# Connectors.net
KiCad netlist of a schematic drawn in Altium Designer
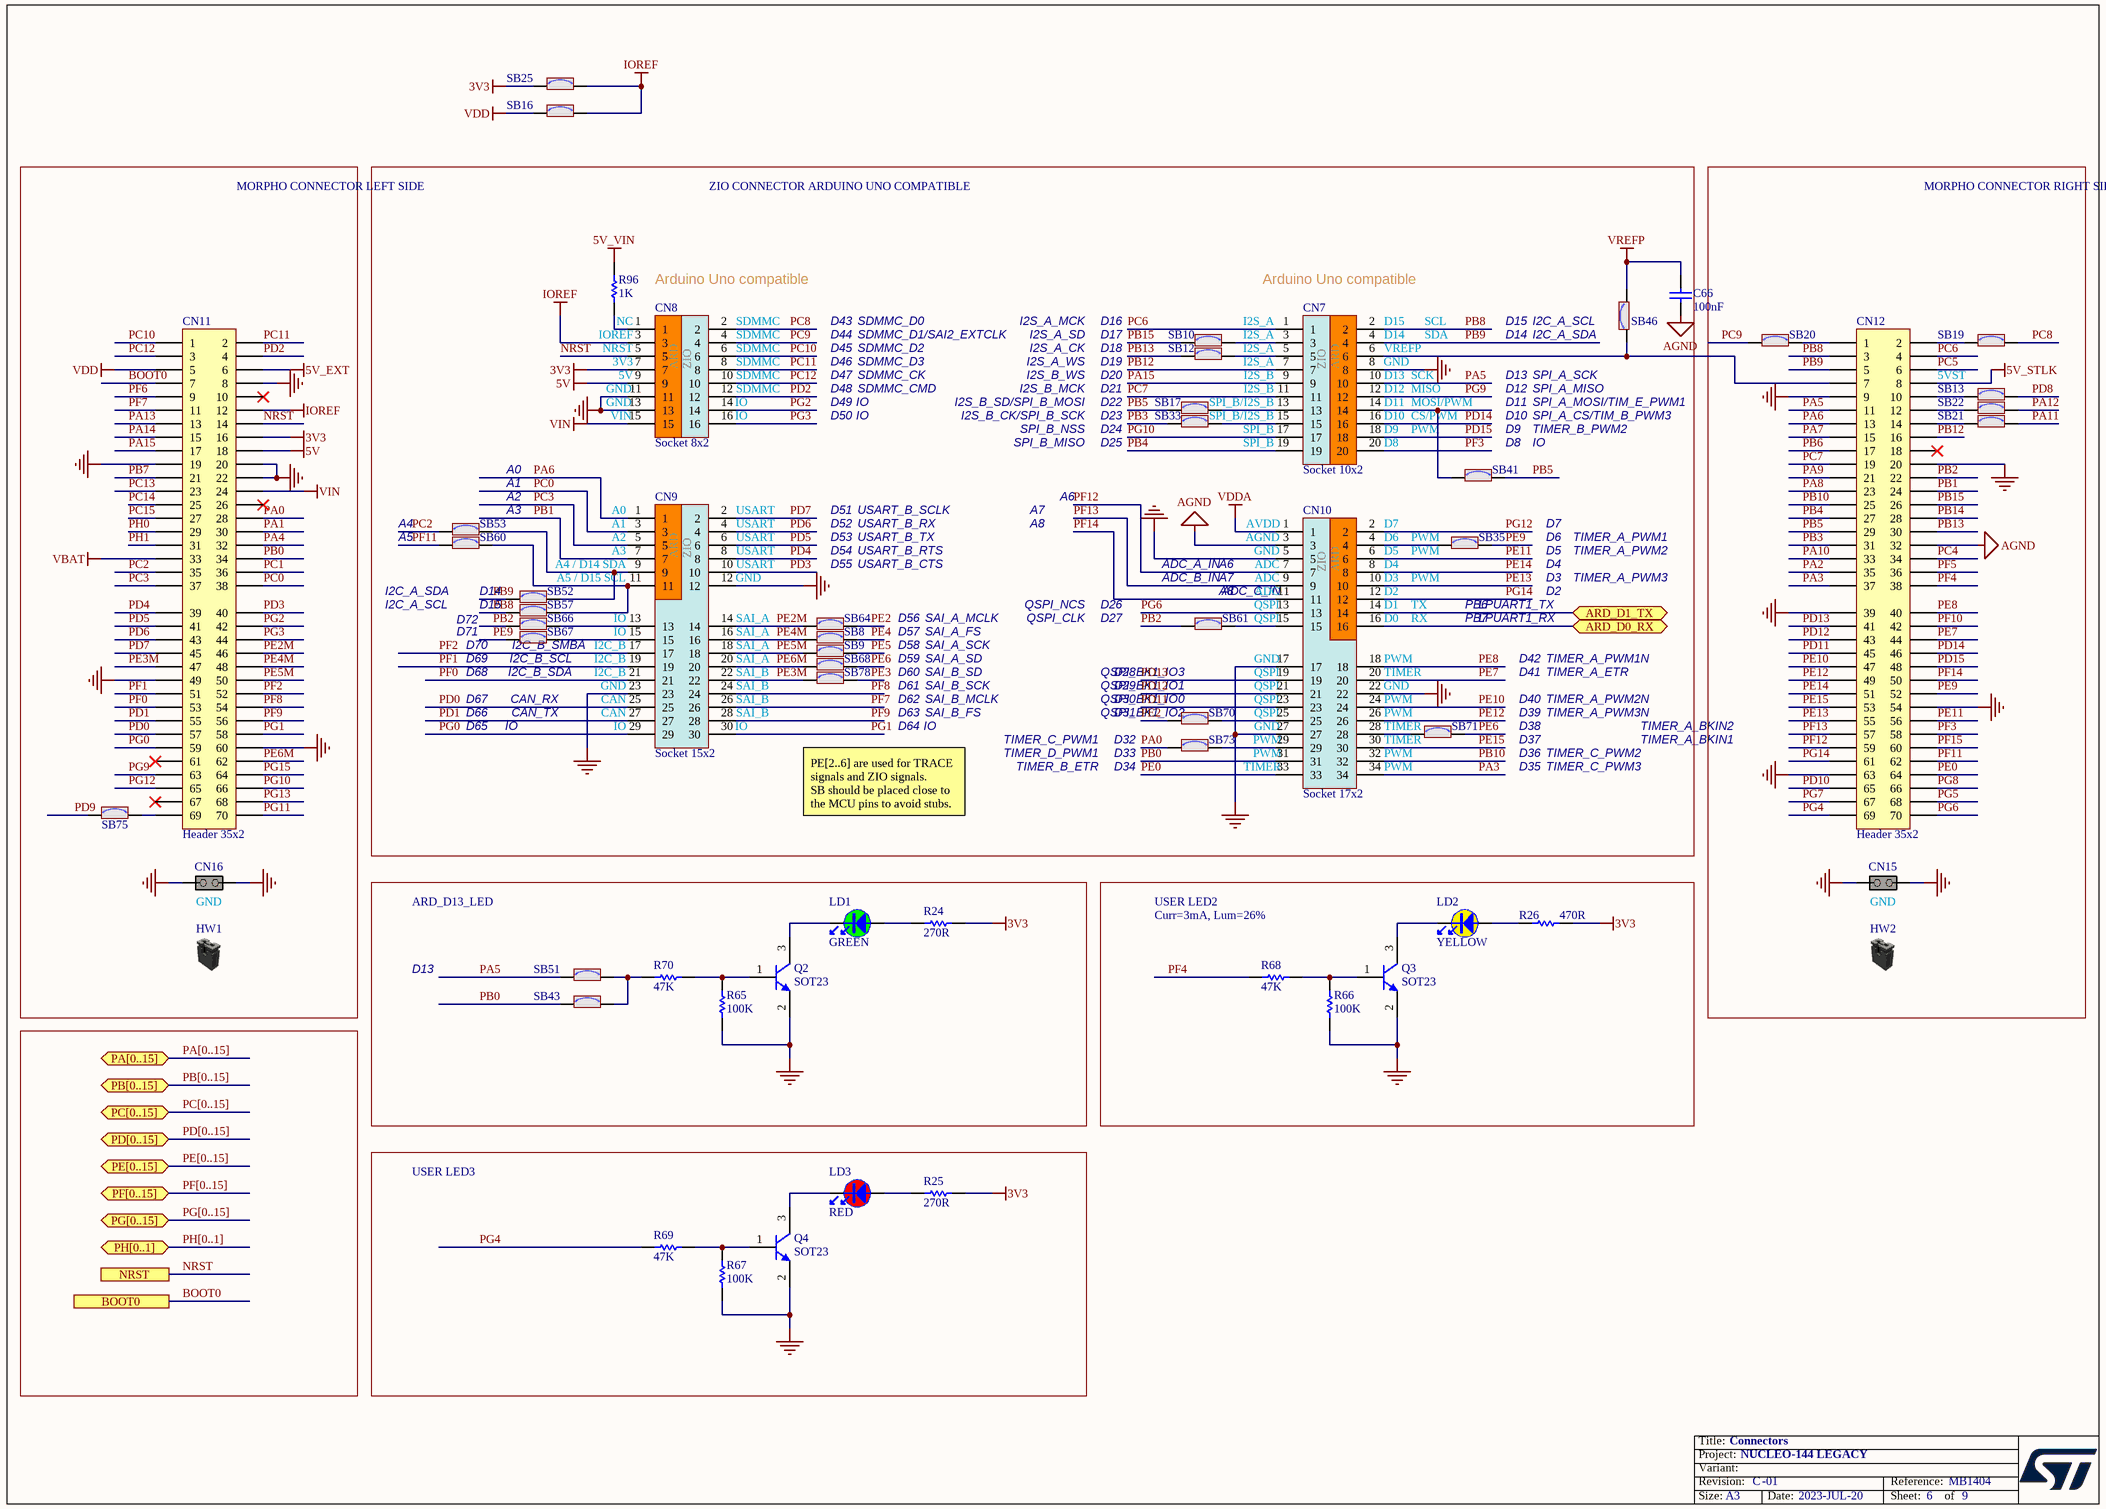
[diagram p0: Connectors.SchDoc]

(export (version "E")
  (design (tool "Eeschema 10.0.6"))
  (components
    (comp (ref "C66")
      (value "100nF")
      (footprint "C0603")
      (description "Capacitor, MLCC, 100nF, 6V3, X5R, +/-10%, 0603, T=0.8mm")
      (fields (field (name "INTERNAL_PART_NUMBER") "MCD-02119") (field (name "MANUFACTURER") "KEMET"))
      (libsource (lib "MCD_PARTS_database") (part "Capacitor"))
    )
    (comp (ref "CN7")
      (value "Socket 10x2")
      (footprint "MCD_PARTS:CON_SAMTEC_SSQ-110-23-F-D")
      (description "Socket, 10x2, 2.54mm, VR, TH, T=8.51mm/10mm")
      (fields (field (name "INTERNAL_PART_NUMBER") "MCD-02953") (field (name "MANUFACTURER") "SAMTEC"))
      (libsource (lib "MCD_PARTS_database") (part "Socket 10x2_N144_ARD"))
    )
    (comp (ref "CN8")
      (value "Socket 8x2")
      (footprint "MCD_PARTS:CON_SAMTEC_SSQ-108-23-F-D")
      (description "Socket, 8x2, 2.54mm, VR, TH, T=8.51mm/10mm")
      (fields (field (name "INTERNAL_PART_NUMBER") "MCD-02951") (field (name "MANUFACTURER") "SAMTEC"))
      (libsource (lib "MCD_PARTS_database") (part "Socket 8x2_N144_ARD"))
    )
    (comp (ref "CN9")
      (value "Socket 15x2")
      (footprint "MCD_PARTS:CON_SAMTEC_SSQ-115-23-F-D")
      (description "Socket, 15x2, 2.54mm, VR, TH, T=8.51mm/10mm")
      (fields (field (name "INTERNAL_PART_NUMBER") "MCD-02952") (field (name "MANUFACTURER") "SAMTEC"))
      (libsource (lib "MCD_PARTS_database") (part "Socket 15x2_N144_ARD"))
    )
    (comp (ref "CN10")
      (value "Socket 17x2")
      (footprint "MCD_PARTS:CON_SAMTEC_SSQ-117-23-F-D")
      (description "Socket, 17x2, 2.54mm, VR, TH, T=8.51mm/10mm")
      (fields (field (name "INTERNAL_PART_NUMBER") "MCD-02954") (field (name "MANUFACTURER") "SAMTEC"))
      (libsource (lib "MCD_PARTS_database") (part "Socket 17x2_N144_ARD"))
    )
    (comp (ref "CN11")
      (value "Header 35x2")
      (footprint "MCD_PARTS:CON_SAMTEC_TSW-135-07-X-D")
      (description "Header, 35x2, 2,54mm, VR, TH, Height 5.84mm/2.54mm")
      (fields
        (field (name "INTERNAL_PART_NUMBER") "MCD-01210")
        (field (name "MANUFACTURER_PART_NUMBER") "TSW-135-07-x-D")
        (field (name "PROVIDED_BY") "SUBCO")
      )
      (libsource (lib "MCD_PARTS_database") (part "Header 35x2"))
    )
    (comp (ref "CN12")
      (value "Header 35x2")
      (footprint "MCD_PARTS:CON_SAMTEC_TSW-135-07-X-D")
      (description "Header, 35x2, 2,54mm, VR, TH, Height 5.84mm/2.54mm")
      (fields
        (field (name "INTERNAL_PART_NUMBER") "MCD-01210")
        (field (name "MANUFACTURER_PART_NUMBER") "TSW-135-07-x-D")
        (field (name "PROVIDED_BY") "SUBCO")
      )
      (libsource (lib "MCD_PARTS_database") (part "Header 35x2"))
    )
    (comp (ref "CN15")
      (value "Jumper_Header 2x1")
      (footprint "MCD_PARTS:CON_SAMTEC_TSW-102-09-X-S")
      (description "Header, 2x1, 2,54mm, VR, TH, Height 5.84mm/10.16mm")
      (fields
        (field (name "INTERNAL_PART_NUMBER") "MCD-00214")
        (field (name "MANUFACTURER_PART_NUMBER") "TSW-102-09-x-S")
        (field (name "PROVIDED_BY") "SUBCO")
      )
      (libsource (lib "MCD_PARTS_database") (part "Jumper_Header 2x1"))
    )
    (comp (ref "CN16")
      (value "Jumper_Header 2x1")
      (footprint "MCD_PARTS:CON_SAMTEC_TSW-102-09-X-S")
      (description "Header, 2x1, 2,54mm, VR, TH, Height 5.84mm/10.16mm")
      (fields
        (field (name "INTERNAL_PART_NUMBER") "MCD-00214")
        (field (name "MANUFACTURER_PART_NUMBER") "TSW-102-09-x-S")
        (field (name "PROVIDED_BY") "SUBCO")
      )
      (libsource (lib "MCD_PARTS_database") (part "Jumper_Header 2x1"))
    )
    (comp (ref "HW1")
      (value "Shunt Black 2.54mm")
      (description "SHUNT 2.54mm BLACK")
      (fields
        (field (name "INTERNAL_PART_NUMBER") "MCD-00043")
        (field (name "MANUFACTURER_PART_NUMBER") "SNT-100-BK-G")
        (field (name "PROVIDED_BY") "SUBCO")
      )
      (libsource (lib "MCD_PARTS_database") (part "Shunt Black 2.54mm"))
    )
    (comp (ref "HW2")
      (value "Shunt Black 2.54mm")
      (description "SHUNT 2.54mm BLACK")
      (fields
        (field (name "INTERNAL_PART_NUMBER") "MCD-00043")
        (field (name "MANUFACTURER_PART_NUMBER") "SNT-100-BK-G")
        (field (name "PROVIDED_BY") "SUBCO")
      )
      (libsource (lib "MCD_PARTS_database") (part "Shunt Black 2.54mm"))
    )
    (comp (ref "LD1")
      (value "GREEN")
      (footprint "MCD_PARTS:LED_0603_OSRAM_LG-Q396-PS-35_GREEN_1A2K_H0P4")
      (description "LED Green, 0603 SMD, Forward Voltage Typ=2V, Max=2.5V")
      (fields
        (field (name "INTERNAL_PART_NUMBER") "MCD-00588")
        (field (name "MANUFACTURER_PART_NUMBER") "LG Q396-PS-35")
        (field (name "PROVIDED_BY") "SUBCO")
      )
      (libsource (lib "MCD_PARTS_database") (part "LED_green"))
    )
    (comp (ref "LD2")
      (value "YELLOW")
      (footprint "MCD_PARTS:LED_0603_OSRAM_LY-Q396-P1Q2-36_YELLOW_1A2K_H0P4")
      (description "LED Yellow, 0603 SMD, Forward Voltage min=1.7V, Typ=2V, Max=2.3V")
      (fields
        (field (name "INTERNAL_PART_NUMBER") "MCD-01061")
        (field (name "MANUFACTURER_PART_NUMBER") "LY Q396-P1Q2-36")
        (field (name "PROVIDED_BY") "SUBCO")
      )
      (libsource (lib "MCD_PARTS_database") (part "LED_yellow"))
    )
    (comp (ref "LD3")
      (value "RED")
      (footprint "MCD_PARTS:LED_0603_OSRAM_LS-Q976-NR-1_RED_1A2K_H0P8")
      (description "LED Red, 0603 SMD, Forward Voltage Typ=2V, Max=2.5V")
      (fields
        (field (name "INTERNAL_PART_NUMBER") "MCD-00586")
        (field (name "MANUFACTURER_PART_NUMBER") "LS Q976-NR-1")
        (field (name "PROVIDED_BY") "SUBCO")
      )
      (libsource (lib "MCD_PARTS_database") (part "LED_red"))
    )
    (comp (ref "Q2")
      (value "SOT23")
      (footprint "MCD_PARTS:NPN_SOT23")
      (description "NPN Bipolar Transistor")
      (fields
        (field (name "INTERNAL_PART_NUMBER") "MCD-00073")
        (field (name "MANUFACTURER_PART_NUMBER") "BSR14")
        (field (name "PROVIDED_BY") "SUBCO")
      )
      (libsource (lib "MCD_PARTS_database") (part "9013-SOT23"))
    )
    (comp (ref "Q3")
      (value "SOT23")
      (footprint "MCD_PARTS:NPN_SOT23")
      (description "NPN Bipolar Transistor")
      (fields
        (field (name "INTERNAL_PART_NUMBER") "MCD-00073")
        (field (name "MANUFACTURER_PART_NUMBER") "BSR14")
        (field (name "PROVIDED_BY") "SUBCO")
      )
      (libsource (lib "MCD_PARTS_database") (part "9013-SOT23"))
    )
    (comp (ref "Q4")
      (value "SOT23")
      (footprint "MCD_PARTS:NPN_SOT23")
      (description "NPN Bipolar Transistor")
      (fields
        (field (name "INTERNAL_PART_NUMBER") "MCD-00073")
        (field (name "MANUFACTURER_PART_NUMBER") "BSR14")
        (field (name "PROVIDED_BY") "SUBCO")
      )
      (libsource (lib "MCD_PARTS_database") (part "9013-SOT23"))
    )
    (comp (ref "R24")
      (value "270R")
      (footprint "MCD_PARTS:R0402")
      (description "Resistor,270R,0402,1%,1/16W")
      (fields
        (field (name "INTERNAL_PART_NUMBER") "MCD-00441")
        (field (name "MANUFACTURER_PART_NUMBER") "RC0402FR-07270RL")
        (field (name "PROVIDED_BY") "SUBCO")
      )
      (libsource (lib "MCD_PARTS_database") (part "Resistor"))
    )
    (comp (ref "R25")
      (value "270R")
      (footprint "MCD_PARTS:R0402")
      (description "Resistor,270R,0402,1%,1/16W")
      (fields
        (field (name "INTERNAL_PART_NUMBER") "MCD-00441")
        (field (name "MANUFACTURER_PART_NUMBER") "RC0402FR-07270RL")
        (field (name "PROVIDED_BY") "SUBCO")
      )
      (libsource (lib "MCD_PARTS_database") (part "Resistor"))
    )
    (comp (ref "R26")
      (value "470R")
      (footprint "MCD_PARTS:R0402")
      (description "Resistor,470R,0402,1%,1/16W")
      (fields
        (field (name "INTERNAL_PART_NUMBER") "MCD-00178")
        (field (name "MANUFACTURER_PART_NUMBER") "RC0402FR-07470RL")
        (field (name "PROVIDED_BY") "SUBCO")
      )
      (libsource (lib "MCD_PARTS_database") (part "Resistor"))
    )
    (comp (ref "R65")
      (value "100K")
      (footprint "MCD_PARTS:R0603")
      (description "Resistor,100K,0603,1%,1/10W")
      (fields
        (field (name "INTERNAL_PART_NUMBER") "MCD-00223")
        (field (name "MANUFACTURER_PART_NUMBER") "RC0603FR-07100KL")
        (field (name "PROVIDED_BY") "SUBCO")
      )
      (libsource (lib "MCD_PARTS_database") (part "Resistor"))
    )
    (comp (ref "R66")
      (value "100K")
      (footprint "MCD_PARTS:R0603")
      (description "Resistor,100K,0603,1%,1/10W")
      (fields
        (field (name "INTERNAL_PART_NUMBER") "MCD-00223")
        (field (name "MANUFACTURER_PART_NUMBER") "RC0603FR-07100KL")
        (field (name "PROVIDED_BY") "SUBCO")
      )
      (libsource (lib "MCD_PARTS_database") (part "Resistor"))
    )
    (comp (ref "R67")
      (value "100K")
      (footprint "MCD_PARTS:R0603")
      (description "Resistor,100K,0603,1%,1/10W")
      (fields
        (field (name "INTERNAL_PART_NUMBER") "MCD-00223")
        (field (name "MANUFACTURER_PART_NUMBER") "RC0603FR-07100KL")
        (field (name "PROVIDED_BY") "SUBCO")
      )
      (libsource (lib "MCD_PARTS_database") (part "Resistor"))
    )
    (comp (ref "R68")
      (value "47K")
      (footprint "MCD_PARTS:R0603")
      (description "Resistor,47K,0603,1%,1/10W")
      (fields
        (field (name "INTERNAL_PART_NUMBER") "MCD-00222")
        (field (name "MANUFACTURER_PART_NUMBER") "RC0603FR-0747KL")
        (field (name "PROVIDED_BY") "SUBCO")
      )
      (libsource (lib "MCD_PARTS_database") (part "Resistor"))
    )
    (comp (ref "R69")
      (value "47K")
      (footprint "MCD_PARTS:R0603")
      (description "Resistor,47K,0603,1%,1/10W")
      (fields
        (field (name "INTERNAL_PART_NUMBER") "MCD-00222")
        (field (name "MANUFACTURER_PART_NUMBER") "RC0603FR-0747KL")
        (field (name "PROVIDED_BY") "SUBCO")
      )
      (libsource (lib "MCD_PARTS_database") (part "Resistor"))
    )
    (comp (ref "R70")
      (value "47K")
      (footprint "MCD_PARTS:R0603")
      (description "Resistor,47K,0603,1%,1/10W")
      (fields
        (field (name "INTERNAL_PART_NUMBER") "MCD-00222")
        (field (name "MANUFACTURER_PART_NUMBER") "RC0603FR-0747KL")
        (field (name "PROVIDED_BY") "SUBCO")
      )
      (libsource (lib "MCD_PARTS_database") (part "Resistor"))
    )
    (comp (ref "R96")
      (value "1K")
      (footprint "MCD_PARTS:R0402")
      (description "Resistor, 1K, 0402, +/-1%,1/16W")
      (fields (field (name "INTERNAL_PART_NUMBER") "MCD-00061") (field (name "MANUFACTURER") "YAGEO"))
      (libsource (lib "MCD_PARTS_database") (part "Resistor"))
    )
    (comp (ref "SB8")
      (value "SB_ON")
      (footprint "MCD_PARTS:SOLDER-BRIDGE_R0402-0R")
      (description "Solder Bridge 0402 ON")
      (fields
        (field (name "INTERNAL_PART_NUMBER") "MCD-01618")
        (field (name "MANUFACTURER_PART_NUMBER") "RC0402JR-070RL")
        (field (name "PROVIDED_BY") "SUBCO")
      )
      (libsource (lib "MCD_PARTS_database") (part "SB_ON"))
    )
    (comp (ref "SB9")
      (value "SB_ON")
      (footprint "MCD_PARTS:SOLDER-BRIDGE_R0402-0R")
      (description "Solder Bridge 0402 ON")
      (fields
        (field (name "INTERNAL_PART_NUMBER") "MCD-01618")
        (field (name "MANUFACTURER_PART_NUMBER") "RC0402JR-070RL")
        (field (name "PROVIDED_BY") "SUBCO")
      )
      (libsource (lib "MCD_PARTS_database") (part "SB_ON"))
    )
    (comp (ref "SB10")
      (value "SB_ON")
      (footprint "MCD_PARTS:SOLDER-BRIDGE_R0603-0R")
      (description "Solder Bridge ON")
      (fields
        (field (name "INTERNAL_PART_NUMBER") "MCD-00071")
        (field (name "MANUFACTURER_PART_NUMBER") "RC0603JR-070RL")
        (field (name "PROVIDED_BY") "SUBCO")
      )
      (libsource (lib "MCD_PARTS_database") (part "SB_ON"))
    )
    (comp (ref "SB12")
      (value "SB_ON")
      (footprint "MCD_PARTS:SOLDER-BRIDGE_R0603-0R")
      (description "Solder Bridge ON")
      (fields
        (field (name "INTERNAL_PART_NUMBER") "MCD-00071")
        (field (name "MANUFACTURER_PART_NUMBER") "RC0603JR-070RL")
        (field (name "PROVIDED_BY") "SUBCO")
      )
      (libsource (lib "MCD_PARTS_database") (part "SB_ON"))
    )
    (comp (ref "SB13")
      (value "SB_ON")
      (footprint "MCD_PARTS:SOLDER-BRIDGE_R0402-0R")
      (description "Solder Bridge 0402 ON")
      (fields
        (field (name "INTERNAL_PART_NUMBER") "MCD-01618")
        (field (name "MANUFACTURER_PART_NUMBER") "RC0402JR-070RL")
        (field (name "PROVIDED_BY") "SUBCO")
      )
      (libsource (lib "MCD_PARTS_database") (part "SB_ON"))
    )
    (comp (ref "SB16")
      (value "SB_ON")
      (footprint "MCD_PARTS:SOLDER-BRIDGE_R0603-0R")
      (description "Solder Bridge ON")
      (fields
        (field (name "INTERNAL_PART_NUMBER") "MCD-00071")
        (field (name "MANUFACTURER_PART_NUMBER") "RC0603JR-070RL")
        (field (name "PROVIDED_BY") "SUBCO")
      )
      (libsource (lib "MCD_PARTS_database") (part "SB_ON"))
    )
    (comp (ref "SB17")
      (value "SB_ON")
      (footprint "MCD_PARTS:SOLDER-BRIDGE_R0603-0R")
      (description "Solder Bridge ON")
      (fields
        (field (name "INTERNAL_PART_NUMBER") "MCD-00071")
        (field (name "MANUFACTURER_PART_NUMBER") "RC0603JR-070RL")
        (field (name "PROVIDED_BY") "SUBCO")
      )
      (libsource (lib "MCD_PARTS_database") (part "SB_ON"))
    )
    (comp (ref "SB19")
      (value "SB_ON")
      (footprint "MCD_PARTS:SOLDER-BRIDGE_R0603-0R")
      (description "Solder Bridge ON")
      (fields
        (field (name "INTERNAL_PART_NUMBER") "MCD-00071")
        (field (name "MANUFACTURER_PART_NUMBER") "RC0603JR-070RL")
        (field (name "PROVIDED_BY") "SUBCO")
      )
      (libsource (lib "MCD_PARTS_database") (part "SB_ON"))
    )
    (comp (ref "SB20")
      (value "SB_ON")
      (footprint "MCD_PARTS:SOLDER-BRIDGE_R0402-0R")
      (description "Solder Bridge 0402 ON")
      (fields
        (field (name "INTERNAL_PART_NUMBER") "MCD-01618")
        (field (name "MANUFACTURER_PART_NUMBER") "RC0402JR-070RL")
        (field (name "PROVIDED_BY") "SUBCO")
      )
      (libsource (lib "MCD_PARTS_database") (part "SB_ON"))
    )
    (comp (ref "SB21")
      (value "SB_ON")
      (footprint "MCD_PARTS:SOLDER-BRIDGE_R0402-0R")
      (description "Solder Bridge 0402 ON")
      (fields
        (field (name "INTERNAL_PART_NUMBER") "MCD-01618")
        (field (name "MANUFACTURER_PART_NUMBER") "RC0402JR-070RL")
        (field (name "PROVIDED_BY") "SUBCO")
      )
      (libsource (lib "MCD_PARTS_database") (part "SB_ON"))
    )
    (comp (ref "SB22")
      (value "SB_ON")
      (footprint "MCD_PARTS:SOLDER-BRIDGE_R0402-0R")
      (description "Solder Bridge 0402 ON")
      (fields
        (field (name "INTERNAL_PART_NUMBER") "MCD-01618")
        (field (name "MANUFACTURER_PART_NUMBER") "RC0402JR-070RL")
        (field (name "PROVIDED_BY") "SUBCO")
      )
      (libsource (lib "MCD_PARTS_database") (part "SB_ON"))
    )
    (comp (ref "SB25")
      (value "SB_ON")
      (footprint "MCD_PARTS:SOLDER-BRIDGE_R0603-0R")
      (description "Solder Bridge ON")
      (fields
        (field (name "INTERNAL_PART_NUMBER") "MCD-00071")
        (field (name "MANUFACTURER_PART_NUMBER") "RC0603JR-070RL")
        (field (name "PROVIDED_BY") "SUBCO")
      )
      (libsource (lib "MCD_PARTS_database") (part "SB_ON"))
    )
    (comp (ref "SB33")
      (value "SB_ON")
      (footprint "MCD_PARTS:SOLDER-BRIDGE_R0402-0R")
      (description "Solder Bridge 0402 ON")
      (fields
        (field (name "INTERNAL_PART_NUMBER") "MCD-01618")
        (field (name "MANUFACTURER_PART_NUMBER") "RC0402JR-070RL")
        (field (name "PROVIDED_BY") "SUBCO")
      )
      (libsource (lib "MCD_PARTS_database") (part "SB_ON"))
    )
    (comp (ref "SB35")
      (value "SB_ON")
      (footprint "MCD_PARTS:SOLDER-BRIDGE_R0402-0R")
      (description "Solder Bridge 0402 ON")
      (fields
        (field (name "INTERNAL_PART_NUMBER") "MCD-01618")
        (field (name "MANUFACTURER_PART_NUMBER") "RC0402JR-070RL")
        (field (name "PROVIDED_BY") "SUBCO")
      )
      (libsource (lib "MCD_PARTS_database") (part "SB_ON"))
    )
    (comp (ref "SB41")
      (value "SB_ON")
      (footprint "MCD_PARTS:SOLDER-BRIDGE_R0603-0R")
      (description "Solder Bridge ON")
      (fields
        (field (name "INTERNAL_PART_NUMBER") "MCD-00071")
        (field (name "MANUFACTURER_PART_NUMBER") "RC0603JR-070RL")
        (field (name "PROVIDED_BY") "SUBCO")
      )
      (libsource (lib "MCD_PARTS_database") (part "SB_ON"))
    )
    (comp (ref "SB43")
      (value "SB_ON")
      (footprint "MCD_PARTS:SOLDER-BRIDGE_R0603-0R")
      (description "Solder Bridge ON")
      (fields
        (field (name "INTERNAL_PART_NUMBER") "MCD-00071")
        (field (name "MANUFACTURER_PART_NUMBER") "RC0603JR-070RL")
        (field (name "PROVIDED_BY") "SUBCO")
      )
      (libsource (lib "MCD_PARTS_database") (part "SB_ON"))
    )
    (comp (ref "SB46")
      (value "SB_ON")
      (footprint "MCD_PARTS:SOLDER-BRIDGE_R0603-0R")
      (description "Solder Bridge ON")
      (fields
        (field (name "INTERNAL_PART_NUMBER") "MCD-00071")
        (field (name "MANUFACTURER_PART_NUMBER") "RC0603JR-070RL")
        (field (name "PROVIDED_BY") "SUBCO")
      )
      (libsource (lib "") (part "SB_ON_1"))
    )
    (comp (ref "SB51")
      (value "SB_ON")
      (footprint "MCD_PARTS:SOLDER-BRIDGE_R0603-0R")
      (description "Solder Bridge ON")
      (fields
        (field (name "INTERNAL_PART_NUMBER") "MCD-00071")
        (field (name "MANUFACTURER_PART_NUMBER") "RC0603JR-070RL")
        (field (name "PROVIDED_BY") "SUBCO")
      )
      (libsource (lib "MCD_PARTS_database") (part "SB_ON"))
    )
    (comp (ref "SB52")
      (value "SB_ON")
      (footprint "MCD_PARTS:SOLDER-BRIDGE_R0402-0R")
      (description "Solder Bridge 0402 ON")
      (fields
        (field (name "INTERNAL_PART_NUMBER") "MCD-01618")
        (field (name "MANUFACTURER_PART_NUMBER") "RC0402JR-070RL")
        (field (name "PROVIDED_BY") "SUBCO")
      )
      (libsource (lib "MCD_PARTS_database") (part "SB_ON"))
    )
    (comp (ref "SB53")
      (value "SB_ON")
      (footprint "MCD_PARTS:SOLDER-BRIDGE_R0402-0R")
      (description "Solder Bridge 0402 ON")
      (fields
        (field (name "INTERNAL_PART_NUMBER") "MCD-01618")
        (field (name "MANUFACTURER_PART_NUMBER") "RC0402JR-070RL")
        (field (name "PROVIDED_BY") "SUBCO")
      )
      (libsource (lib "MCD_PARTS_database") (part "SB_ON"))
    )
    (comp (ref "SB57")
      (value "SB_ON")
      (footprint "MCD_PARTS:SOLDER-BRIDGE_R0402-0R")
      (description "Solder Bridge 0402 ON")
      (fields
        (field (name "INTERNAL_PART_NUMBER") "MCD-01618")
        (field (name "MANUFACTURER_PART_NUMBER") "RC0402JR-070RL")
        (field (name "PROVIDED_BY") "SUBCO")
      )
      (libsource (lib "MCD_PARTS_database") (part "SB_ON"))
    )
    (comp (ref "SB60")
      (value "SB_ON")
      (footprint "MCD_PARTS:SOLDER-BRIDGE_R0402-0R")
      (description "Solder Bridge 0402 ON")
      (fields
        (field (name "INTERNAL_PART_NUMBER") "MCD-01618")
        (field (name "MANUFACTURER_PART_NUMBER") "RC0402JR-070RL")
        (field (name "PROVIDED_BY") "SUBCO")
      )
      (libsource (lib "MCD_PARTS_database") (part "SB_ON"))
    )
    (comp (ref "SB61")
      (value "SB_ON")
      (footprint "MCD_PARTS:SOLDER-BRIDGE_R0402-0R")
      (description "Solder Bridge 0402 ON")
      (fields
        (field (name "INTERNAL_PART_NUMBER") "MCD-01618")
        (field (name "MANUFACTURER_PART_NUMBER") "RC0402JR-070RL")
        (field (name "PROVIDED_BY") "SUBCO")
      )
      (libsource (lib "MCD_PARTS_database") (part "SB_ON"))
    )
    (comp (ref "SB64")
      (value "SB_ON")
      (footprint "MCD_PARTS:SOLDER-BRIDGE_R0402-0R")
      (description "Solder Bridge 0402 ON")
      (fields
        (field (name "INTERNAL_PART_NUMBER") "MCD-01618")
        (field (name "MANUFACTURER_PART_NUMBER") "RC0402JR-070RL")
        (field (name "PROVIDED_BY") "SUBCO")
      )
      (libsource (lib "MCD_PARTS_database") (part "SB_ON"))
    )
    (comp (ref "SB66")
      (value "SB_ON")
      (footprint "MCD_PARTS:SOLDER-BRIDGE_R0402-0R")
      (description "Solder Bridge 0402 ON")
      (fields
        (field (name "INTERNAL_PART_NUMBER") "MCD-01618")
        (field (name "MANUFACTURER_PART_NUMBER") "RC0402JR-070RL")
        (field (name "PROVIDED_BY") "SUBCO")
      )
      (libsource (lib "MCD_PARTS_database") (part "SB_ON"))
    )
    (comp (ref "SB67")
      (value "SB_ON")
      (footprint "MCD_PARTS:SOLDER-BRIDGE_R0402-0R")
      (description "Solder Bridge 0402 ON")
      (fields
        (field (name "INTERNAL_PART_NUMBER") "MCD-01618")
        (field (name "MANUFACTURER_PART_NUMBER") "RC0402JR-070RL")
        (field (name "PROVIDED_BY") "SUBCO")
      )
      (libsource (lib "MCD_PARTS_database") (part "SB_ON"))
    )
    (comp (ref "SB68")
      (value "SB_ON")
      (footprint "MCD_PARTS:SOLDER-BRIDGE_R0402-0R")
      (description "Solder Bridge 0402 ON")
      (fields
        (field (name "INTERNAL_PART_NUMBER") "MCD-01618")
        (field (name "MANUFACTURER_PART_NUMBER") "RC0402JR-070RL")
        (field (name "PROVIDED_BY") "SUBCO")
      )
      (libsource (lib "MCD_PARTS_database") (part "SB_ON"))
    )
    (comp (ref "SB70")
      (value "SB_ON")
      (footprint "MCD_PARTS:SOLDER-BRIDGE_R0402-0R")
      (description "Solder Bridge 0402 ON")
      (fields
        (field (name "INTERNAL_PART_NUMBER") "MCD-01618")
        (field (name "MANUFACTURER_PART_NUMBER") "RC0402JR-070RL")
        (field (name "PROVIDED_BY") "SUBCO")
      )
      (libsource (lib "MCD_PARTS_database") (part "SB_ON"))
    )
    (comp (ref "SB71")
      (value "SB_ON")
      (footprint "MCD_PARTS:SOLDER-BRIDGE_R0402-0R")
      (description "Solder Bridge 0402 ON")
      (fields
        (field (name "INTERNAL_PART_NUMBER") "MCD-01618")
        (field (name "MANUFACTURER_PART_NUMBER") "RC0402JR-070RL")
        (field (name "PROVIDED_BY") "SUBCO")
      )
      (libsource (lib "MCD_PARTS_database") (part "SB_ON"))
    )
    (comp (ref "SB73")
      (value "SB_ON")
      (footprint "MCD_PARTS:SOLDER-BRIDGE_R0402-0R")
      (description "Solder Bridge 0402 ON")
      (fields
        (field (name "INTERNAL_PART_NUMBER") "MCD-01618")
        (field (name "MANUFACTURER_PART_NUMBER") "RC0402JR-070RL")
        (field (name "PROVIDED_BY") "SUBCO")
      )
      (libsource (lib "MCD_PARTS_database") (part "SB_ON"))
    )
    (comp (ref "SB75")
      (value "SB_ON")
      (footprint "MCD_PARTS:SOLDER-BRIDGE_R0402-0R")
      (description "Solder Bridge 0402 ON")
      (fields
        (field (name "INTERNAL_PART_NUMBER") "MCD-01618")
        (field (name "MANUFACTURER_PART_NUMBER") "RC0402JR-070RL")
        (field (name "PROVIDED_BY") "SUBCO")
      )
      (libsource (lib "MCD_PARTS_database") (part "SB_ON"))
    )
    (comp (ref "SB78")
      (value "SB_ON")
      (footprint "MCD_PARTS:SOLDER-BRIDGE_R0402-0R")
      (description "Solder Bridge 0402 ON")
      (fields
        (field (name "INTERNAL_PART_NUMBER") "MCD-01618")
        (field (name "MANUFACTURER_PART_NUMBER") "RC0402JR-070RL")
        (field (name "PROVIDED_BY") "SUBCO")
      )
      (libsource (lib "MCD_PARTS_database") (part "SB_ON"))
    )
  )
  (nets
    (net (code "3") (name "/ARD_D0_RX") (class "Default")
      (node (ref "CN10") (pin "16") (pinfunction "16_16") (pintype "passive"))
    )
    (net (code "4") (name "/ARD_D1_TX") (class "Default")
      (node (ref "CN10") (pin "14") (pinfunction "14_14") (pintype "passive"))
    )
    (net (code "5") (name "/BOOT0") (class "Default")
      (node (ref "CN11") (pin "7") (pinfunction "7_7") (pintype "passive"))
    )
    (net (code "6") (name "/NRST") (class "Default")
      (node (ref "CN11") (pin "14") (pinfunction "14_14") (pintype "passive"))
      (node (ref "CN8") (pin "5") (pinfunction "5_5") (pintype "passive"))
    )
    (net (code "7") (name "/PA0") (class "Default")
      (node (ref "CN11") (pin "28") (pinfunction "28_28") (pintype "passive"))
      (node (ref "SB73") (pin "1") (pinfunction "1_1") (pintype "passive"))
    )
    (net (code "8") (name "/PA1") (class "Default")
      (node (ref "CN11") (pin "30") (pinfunction "30_30") (pintype "passive"))
    )
    (net (code "9") (name "/PA2") (class "Default")
      (node (ref "CN12") (pin "35") (pinfunction "35_35") (pintype "passive"))
    )
    (net (code "10") (name "/PA3") (class "Default")
      (node (ref "CN10") (pin "34") (pinfunction "34_34") (pintype "passive"))
      (node (ref "CN12") (pin "37") (pinfunction "37_37") (pintype "passive"))
    )
    (net (code "11") (name "/PA4") (class "Default")
      (node (ref "CN11") (pin "32") (pinfunction "32_32") (pintype "passive"))
    )
    (net (code "12") (name "/PA5") (class "Default")
      (node (ref "CN12") (pin "11") (pinfunction "11_11") (pintype "passive"))
      (node (ref "CN7") (pin "10") (pinfunction "10_10") (pintype "passive"))
      (node (ref "SB51") (pin "1") (pinfunction "1_1") (pintype "passive"))
    )
    (net (code "13") (name "/PA6") (class "Default")
      (node (ref "CN12") (pin "13") (pinfunction "13_13") (pintype "passive"))
      (node (ref "CN9") (pin "1") (pinfunction "1_1") (pintype "passive"))
    )
    (net (code "14") (name "/PA7") (class "Default")
      (node (ref "CN12") (pin "15") (pinfunction "15_15") (pintype "passive"))
    )
    (net (code "15") (name "/PA8") (class "Default")
      (node (ref "CN12") (pin "23") (pinfunction "23_23") (pintype "passive"))
    )
    (net (code "16") (name "/PA9") (class "Default")
      (node (ref "CN12") (pin "21") (pinfunction "21_21") (pintype "passive"))
    )
    (net (code "17") (name "/PA10") (class "Default")
      (node (ref "CN12") (pin "33") (pinfunction "33_33") (pintype "passive"))
    )
    (net (code "18") (name "/PA11") (class "Default")
      (node (ref "SB21") (pin "2") (pinfunction "2_2") (pintype "passive"))
    )
    (net (code "19") (name "/PA12") (class "Default")
      (node (ref "SB22") (pin "2") (pinfunction "2_2") (pintype "passive"))
    )
    (net (code "20") (name "/PA13") (class "Default")
      (node (ref "CN11") (pin "13") (pinfunction "13_13") (pintype "passive"))
    )
    (net (code "21") (name "/PA14") (class "Default")
      (node (ref "CN11") (pin "15") (pinfunction "15_15") (pintype "passive"))
    )
    (net (code "22") (name "/PA15") (class "Default")
      (node (ref "CN11") (pin "17") (pinfunction "17_17") (pintype "passive"))
      (node (ref "CN7") (pin "9") (pinfunction "9_9") (pintype "passive"))
    )
    (net (code "24") (name "/PB0") (class "Default")
      (node (ref "CN10") (pin "31") (pinfunction "31_31") (pintype "passive"))
      (node (ref "CN11") (pin "34") (pinfunction "34_34") (pintype "passive"))
      (node (ref "SB43") (pin "1") (pinfunction "1_1") (pintype "passive"))
    )
    (net (code "25") (name "/PB1") (class "Default")
      (node (ref "CN12") (pin "24") (pinfunction "24_24") (pintype "passive"))
      (node (ref "CN9") (pin "7") (pinfunction "7_7") (pintype "passive"))
    )
    (net (code "26") (name "/PB2") (class "Default")
      (node (ref "CN12") (pin "22") (pinfunction "22_22") (pintype "passive"))
      (node (ref "SB61") (pin "1") (pinfunction "1_1") (pintype "passive"))
      (node (ref "SB66") (pin "1") (pinfunction "1_1") (pintype "passive"))
    )
    (net (code "27") (name "/PB3") (class "Default")
      (node (ref "CN12") (pin "31") (pinfunction "31_31") (pintype "passive"))
      (node (ref "SB33") (pin "1") (pinfunction "1_1") (pintype "passive"))
    )
    (net (code "28") (name "/PB4") (class "Default")
      (node (ref "CN12") (pin "27") (pinfunction "27_27") (pintype "passive"))
      (node (ref "CN7") (pin "19") (pinfunction "19_19") (pintype "passive"))
    )
    (net (code "29") (name "/PB5") (class "Default")
      (node (ref "CN12") (pin "29") (pinfunction "29_29") (pintype "passive"))
      (node (ref "SB17") (pin "1") (pinfunction "1_1") (pintype "passive"))
      (node (ref "SB41") (pin "2") (pinfunction "2_2") (pintype "passive"))
    )
    (net (code "30") (name "/PB6") (class "Default")
      (node (ref "CN12") (pin "17") (pinfunction "17_17") (pintype "passive"))
    )
    (net (code "31") (name "/PB7") (class "Default")
      (node (ref "CN11") (pin "21") (pinfunction "21_21") (pintype "passive"))
    )
    (net (code "32") (name "/PB8") (class "Default")
      (node (ref "CN12") (pin "3") (pinfunction "3_3") (pintype "passive"))
      (node (ref "CN7") (pin "2") (pinfunction "2_2") (pintype "passive"))
      (node (ref "SB57") (pin "1") (pinfunction "1_1") (pintype "passive"))
    )
    (net (code "33") (name "/PB9") (class "Default")
      (node (ref "CN12") (pin "5") (pinfunction "5_5") (pintype "passive"))
      (node (ref "CN7") (pin "4") (pinfunction "4_4") (pintype "passive"))
      (node (ref "SB52") (pin "1") (pinfunction "1_1") (pintype "passive"))
    )
    (net (code "34") (name "/PB10") (class "Default")
      (node (ref "CN10") (pin "32") (pinfunction "32_32") (pintype "passive"))
      (node (ref "CN12") (pin "25") (pinfunction "25_25") (pintype "passive"))
    )
    (net (code "35") (name "/PB12") (class "Default")
      (node (ref "CN12") (pin "16") (pinfunction "16_16") (pintype "passive"))
      (node (ref "CN7") (pin "7") (pinfunction "7_7") (pintype "passive"))
    )
    (net (code "36") (name "/PB13") (class "Default")
      (node (ref "CN12") (pin "30") (pinfunction "30_30") (pintype "passive"))
      (node (ref "SB12") (pin "1") (pinfunction "1_1") (pintype "passive"))
    )
    (net (code "37") (name "/PB14") (class "Default")
      (node (ref "CN12") (pin "28") (pinfunction "28_28") (pintype "passive"))
    )
    (net (code "38") (name "/PB15") (class "Default")
      (node (ref "CN12") (pin "26") (pinfunction "26_26") (pintype "passive"))
      (node (ref "SB10") (pin "1") (pinfunction "1_1") (pintype "passive"))
    )
    (net (code "40") (name "/PC0") (class "Default")
      (node (ref "CN11") (pin "38") (pinfunction "38_38") (pintype "passive"))
      (node (ref "CN9") (pin "3") (pinfunction "3_3") (pintype "passive"))
    )
    (net (code "41") (name "/PC1") (class "Default")
      (node (ref "CN11") (pin "36") (pinfunction "36_36") (pintype "passive"))
    )
    (net (code "42") (name "/PC2") (class "Default")
      (node (ref "CN11") (pin "35") (pinfunction "35_35") (pintype "passive"))
      (node (ref "SB53") (pin "1") (pinfunction "1_1") (pintype "passive"))
    )
    (net (code "43") (name "/PC3") (class "Default")
      (node (ref "CN11") (pin "37") (pinfunction "37_37") (pintype "passive"))
      (node (ref "CN9") (pin "5") (pinfunction "5_5") (pintype "passive"))
    )
    (net (code "44") (name "/PC4") (class "Default")
      (node (ref "CN12") (pin "34") (pinfunction "34_34") (pintype "passive"))
    )
    (net (code "45") (name "/PC5") (class "Default")
      (node (ref "CN12") (pin "6") (pinfunction "6_6") (pintype "passive"))
    )
    (net (code "46") (name "/PC6") (class "Default")
      (node (ref "CN12") (pin "4") (pinfunction "4_4") (pintype "passive"))
      (node (ref "CN7") (pin "1") (pinfunction "1_1") (pintype "passive"))
    )
    (net (code "47") (name "/PC7") (class "Default")
      (node (ref "CN12") (pin "19") (pinfunction "19_19") (pintype "passive"))
      (node (ref "CN7") (pin "11") (pinfunction "11_11") (pintype "passive"))
    )
    (net (code "48") (name "/PC8") (class "Default")
      (node (ref "CN8") (pin "2") (pinfunction "2_2") (pintype "passive"))
      (node (ref "SB19") (pin "2") (pinfunction "2_2") (pintype "passive"))
    )
    (net (code "49") (name "/PC9") (class "Default")
      (node (ref "CN8") (pin "4") (pinfunction "4_4") (pintype "passive"))
      (node (ref "SB20") (pin "1") (pinfunction "1_1") (pintype "passive"))
    )
    (net (code "50") (name "/PC10") (class "Default")
      (node (ref "CN11") (pin "1") (pinfunction "1_1") (pintype "passive"))
      (node (ref "CN8") (pin "6") (pinfunction "6_6") (pintype "passive"))
    )
    (net (code "51") (name "/PC11") (class "Default")
      (node (ref "CN11") (pin "2") (pinfunction "2_2") (pintype "passive"))
      (node (ref "CN8") (pin "8") (pinfunction "8_8") (pintype "passive"))
    )
    (net (code "52") (name "/PC12") (class "Default")
      (node (ref "CN11") (pin "3") (pinfunction "3_3") (pintype "passive"))
      (node (ref "CN8") (pin "10") (pinfunction "10_10") (pintype "passive"))
    )
    (net (code "53") (name "/PC13") (class "Default")
      (node (ref "CN11") (pin "23") (pinfunction "23_23") (pintype "passive"))
    )
    (net (code "54") (name "/PC14") (class "Default")
      (node (ref "CN11") (pin "25") (pinfunction "25_25") (pintype "passive"))
    )
    (net (code "55") (name "/PC15") (class "Default")
      (node (ref "CN11") (pin "27") (pinfunction "27_27") (pintype "passive"))
    )
    (net (code "57") (name "/PD0") (class "Default")
      (node (ref "CN11") (pin "57") (pinfunction "57_57") (pintype "passive"))
      (node (ref "CN9") (pin "25") (pinfunction "25_25") (pintype "passive"))
    )
    (net (code "58") (name "/PD1") (class "Default")
      (node (ref "CN11") (pin "55") (pinfunction "55_55") (pintype "passive"))
      (node (ref "CN9") (pin "27") (pinfunction "27_27") (pintype "passive"))
    )
    (net (code "59") (name "/PD2") (class "Default")
      (node (ref "CN11") (pin "4") (pinfunction "4_4") (pintype "passive"))
      (node (ref "CN8") (pin "12") (pinfunction "12_12") (pintype "passive"))
    )
    (net (code "60") (name "/PD3") (class "Default")
      (node (ref "CN11") (pin "40") (pinfunction "40_40") (pintype "passive"))
      (node (ref "CN9") (pin "10") (pinfunction "10_10") (pintype "passive"))
    )
    (net (code "61") (name "/PD4") (class "Default")
      (node (ref "CN11") (pin "39") (pinfunction "39_39") (pintype "passive"))
      (node (ref "CN9") (pin "8") (pinfunction "8_8") (pintype "passive"))
    )
    (net (code "62") (name "/PD5") (class "Default")
      (node (ref "CN11") (pin "41") (pinfunction "41_41") (pintype "passive"))
      (node (ref "CN9") (pin "6") (pinfunction "6_6") (pintype "passive"))
    )
    (net (code "63") (name "/PD6") (class "Default")
      (node (ref "CN11") (pin "43") (pinfunction "43_43") (pintype "passive"))
      (node (ref "CN9") (pin "4") (pinfunction "4_4") (pintype "passive"))
    )
    (net (code "64") (name "/PD7") (class "Default")
      (node (ref "CN11") (pin "45") (pinfunction "45_45") (pintype "passive"))
      (node (ref "CN9") (pin "2") (pinfunction "2_2") (pintype "passive"))
    )
    (net (code "65") (name "/PD8") (class "Default")
      (node (ref "SB13") (pin "2") (pinfunction "2_2") (pintype "passive"))
    )
    (net (code "66") (name "/PD9") (class "Default")
      (node (ref "SB75") (pin "1") (pinfunction "1_1") (pintype "passive"))
    )
    (net (code "67") (name "/PD10") (class "Default")
      (node (ref "CN12") (pin "65") (pinfunction "65_65") (pintype "passive"))
    )
    (net (code "68") (name "/PD11") (class "Default")
      (node (ref "CN10") (pin "23") (pinfunction "23_23") (pintype "passive"))
      (node (ref "CN12") (pin "45") (pinfunction "45_45") (pintype "passive"))
    )
    (net (code "69") (name "/PD12") (class "Default")
      (node (ref "CN10") (pin "21") (pinfunction "21_21") (pintype "passive"))
      (node (ref "CN12") (pin "43") (pinfunction "43_43") (pintype "passive"))
    )
    (net (code "70") (name "/PD13") (class "Default")
      (node (ref "CN10") (pin "19") (pinfunction "19_19") (pintype "passive"))
      (node (ref "CN12") (pin "41") (pinfunction "41_41") (pintype "passive"))
    )
    (net (code "71") (name "/PD14") (class "Default")
      (node (ref "CN12") (pin "46") (pinfunction "46_46") (pintype "passive"))
      (node (ref "CN7") (pin "16") (pinfunction "16_16") (pintype "passive"))
    )
    (net (code "72") (name "/PD15") (class "Default")
      (node (ref "CN12") (pin "48") (pinfunction "48_48") (pintype "passive"))
      (node (ref "CN7") (pin "18") (pinfunction "18_18") (pintype "passive"))
    )
    (net (code "74") (name "/PE0") (class "Default")
      (node (ref "CN10") (pin "33") (pinfunction "33_33") (pintype "passive"))
      (node (ref "CN12") (pin "64") (pinfunction "64_64") (pintype "passive"))
    )
    (net (code "75") (name "/PE2") (class "Default")
      (node (ref "SB64") (pin "2") (pinfunction "2_2") (pintype "passive"))
      (node (ref "SB70") (pin "1") (pinfunction "1_1") (pintype "passive"))
    )
    (net (code "76") (name "/PE2M") (class "Default")
      (node (ref "CN11") (pin "46") (pinfunction "46_46") (pintype "passive"))
      (node (ref "CN9") (pin "14") (pinfunction "14_14") (pintype "passive"))
      (node (ref "SB64") (pin "1") (pinfunction "1_1") (pintype "passive"))
    )
    (net (code "77") (name "/PE3") (class "Default")
      (node (ref "SB78") (pin "2") (pinfunction "2_2") (pintype "passive"))
    )
    (net (code "78") (name "/PE3M") (class "Default")
      (node (ref "CN11") (pin "47") (pinfunction "47_47") (pintype "passive"))
      (node (ref "CN9") (pin "22") (pinfunction "22_22") (pintype "passive"))
      (node (ref "SB78") (pin "1") (pinfunction "1_1") (pintype "passive"))
    )
    (net (code "79") (name "/PE4") (class "Default")
      (node (ref "SB8") (pin "2") (pinfunction "2_2") (pintype "passive"))
    )
    (net (code "80") (name "/PE4M") (class "Default")
      (node (ref "CN11") (pin "48") (pinfunction "48_48") (pintype "passive"))
      (node (ref "CN9") (pin "16") (pinfunction "16_16") (pintype "passive"))
      (node (ref "SB8") (pin "1") (pinfunction "1_1") (pintype "passive"))
    )
    (net (code "81") (name "/PE5") (class "Default")
      (node (ref "SB9") (pin "2") (pinfunction "2_2") (pintype "passive"))
    )
    (net (code "82") (name "/PE5M") (class "Default")
      (node (ref "CN11") (pin "50") (pinfunction "50_50") (pintype "passive"))
      (node (ref "CN9") (pin "18") (pinfunction "18_18") (pintype "passive"))
      (node (ref "SB9") (pin "1") (pinfunction "1_1") (pintype "passive"))
    )
    (net (code "83") (name "/PE6") (class "Default")
      (node (ref "SB68") (pin "2") (pinfunction "2_2") (pintype "passive"))
      (node (ref "SB71") (pin "2") (pinfunction "2_2") (pintype "passive"))
    )
    (net (code "84") (name "/PE6M") (class "Default")
      (node (ref "CN11") (pin "62") (pinfunction "62_62") (pintype "passive"))
      (node (ref "CN9") (pin "20") (pinfunction "20_20") (pintype "passive"))
      (node (ref "SB68") (pin "1") (pinfunction "1_1") (pintype "passive"))
    )
    (net (code "85") (name "/PE7") (class "Default")
      (node (ref "CN10") (pin "20") (pinfunction "20_20") (pintype "passive"))
      (node (ref "CN12") (pin "44") (pinfunction "44_44") (pintype "passive"))
    )
    (net (code "86") (name "/PE8") (class "Default")
      (node (ref "CN10") (pin "18") (pinfunction "18_18") (pintype "passive"))
      (node (ref "CN12") (pin "40") (pinfunction "40_40") (pintype "passive"))
    )
    (net (code "87") (name "/PE9") (class "Default")
      (node (ref "CN12") (pin "52") (pinfunction "52_52") (pintype "passive"))
      (node (ref "SB35") (pin "2") (pinfunction "2_2") (pintype "passive"))
      (node (ref "SB67") (pin "1") (pinfunction "1_1") (pintype "passive"))
    )
    (net (code "88") (name "/PE10") (class "Default")
      (node (ref "CN10") (pin "24") (pinfunction "24_24") (pintype "passive"))
      (node (ref "CN12") (pin "47") (pinfunction "47_47") (pintype "passive"))
    )
    (net (code "89") (name "/PE11") (class "Default")
      (node (ref "CN10") (pin "6") (pinfunction "6_6") (pintype "passive"))
      (node (ref "CN12") (pin "56") (pinfunction "56_56") (pintype "passive"))
    )
    (net (code "90") (name "/PE12") (class "Default")
      (node (ref "CN10") (pin "26") (pinfunction "26_26") (pintype "passive"))
      (node (ref "CN12") (pin "49") (pinfunction "49_49") (pintype "passive"))
    )
    (net (code "91") (name "/PE13") (class "Default")
      (node (ref "CN10") (pin "10") (pinfunction "10_10") (pintype "passive"))
      (node (ref "CN12") (pin "55") (pinfunction "55_55") (pintype "passive"))
    )
    (net (code "92") (name "/PE14") (class "Default")
      (node (ref "CN10") (pin "8") (pinfunction "8_8") (pintype "passive"))
      (node (ref "CN12") (pin "51") (pinfunction "51_51") (pintype "passive"))
    )
    (net (code "93") (name "/PE15") (class "Default")
      (node (ref "CN10") (pin "30") (pinfunction "30_30") (pintype "passive"))
      (node (ref "CN12") (pin "53") (pinfunction "53_53") (pintype "passive"))
    )
    (net (code "95") (name "/PF0") (class "Default")
      (node (ref "CN11") (pin "53") (pinfunction "53_53") (pintype "passive"))
      (node (ref "CN9") (pin "21") (pinfunction "21_21") (pintype "passive"))
    )
    (net (code "96") (name "/PF1") (class "Default")
      (node (ref "CN11") (pin "51") (pinfunction "51_51") (pintype "passive"))
      (node (ref "CN9") (pin "19") (pinfunction "19_19") (pintype "passive"))
    )
    (net (code "97") (name "/PF2") (class "Default")
      (node (ref "CN11") (pin "52") (pinfunction "52_52") (pintype "passive"))
      (node (ref "CN9") (pin "17") (pinfunction "17_17") (pintype "passive"))
    )
    (net (code "98") (name "/PF3") (class "Default")
      (node (ref "CN12") (pin "58") (pinfunction "58_58") (pintype "passive"))
      (node (ref "CN7") (pin "20") (pinfunction "20_20") (pintype "passive"))
    )
    (net (code "99") (name "/PF4") (class "Default")
      (node (ref "CN12") (pin "38") (pinfunction "38_38") (pintype "passive"))
      (node (ref "R68") (pin "1") (pinfunction "1_1") (pintype "passive"))
    )
    (net (code "100") (name "/PF5") (class "Default")
      (node (ref "CN12") (pin "36") (pinfunction "36_36") (pintype "passive"))
    )
    (net (code "101") (name "/PF6") (class "Default")
      (node (ref "CN11") (pin "9") (pinfunction "9_9") (pintype "passive"))
    )
    (net (code "102") (name "/PF7") (class "Default")
      (node (ref "CN11") (pin "11") (pinfunction "11_11") (pintype "passive"))
      (node (ref "CN9") (pin "26") (pinfunction "26_26") (pintype "passive"))
    )
    (net (code "103") (name "/PF8") (class "Default")
      (node (ref "CN11") (pin "54") (pinfunction "54_54") (pintype "passive"))
      (node (ref "CN9") (pin "24") (pinfunction "24_24") (pintype "passive"))
    )
    (net (code "104") (name "/PF9") (class "Default")
      (node (ref "CN11") (pin "56") (pinfunction "56_56") (pintype "passive"))
      (node (ref "CN9") (pin "28") (pinfunction "28_28") (pintype "passive"))
    )
    (net (code "105") (name "/PF10") (class "Default")
      (node (ref "CN12") (pin "42") (pinfunction "42_42") (pintype "passive"))
    )
    (net (code "106") (name "/PF11") (class "Default")
      (node (ref "CN12") (pin "62") (pinfunction "62_62") (pintype "passive"))
      (node (ref "SB60") (pin "1") (pinfunction "1_1") (pintype "passive"))
    )
    (net (code "107") (name "/PF12") (class "Default")
      (node (ref "CN10") (pin "7") (pinfunction "7_7") (pintype "passive"))
      (node (ref "CN12") (pin "59") (pinfunction "59_59") (pintype "passive"))
    )
    (net (code "108") (name "/PF13") (class "Default")
      (node (ref "CN10") (pin "9") (pinfunction "9_9") (pintype "passive"))
      (node (ref "CN12") (pin "57") (pinfunction "57_57") (pintype "passive"))
    )
    (net (code "109") (name "/PF14") (class "Default")
      (node (ref "CN10") (pin "11") (pinfunction "11_11") (pintype "passive"))
      (node (ref "CN12") (pin "50") (pinfunction "50_50") (pintype "passive"))
    )
    (net (code "110") (name "/PF15") (class "Default")
      (node (ref "CN12") (pin "60") (pinfunction "60_60") (pintype "passive"))
    )
    (net (code "112") (name "/PG0") (class "Default")
      (node (ref "CN11") (pin "59") (pinfunction "59_59") (pintype "passive"))
      (node (ref "CN9") (pin "29") (pinfunction "29_29") (pintype "passive"))
    )
    (net (code "113") (name "/PG1") (class "Default")
      (node (ref "CN11") (pin "58") (pinfunction "58_58") (pintype "passive"))
      (node (ref "CN9") (pin "30") (pinfunction "30_30") (pintype "passive"))
    )
    (net (code "114") (name "/PG2") (class "Default")
      (node (ref "CN11") (pin "42") (pinfunction "42_42") (pintype "passive"))
      (node (ref "CN8") (pin "14") (pinfunction "14_14") (pintype "passive"))
    )
    (net (code "115") (name "/PG3") (class "Default")
      (node (ref "CN11") (pin "44") (pinfunction "44_44") (pintype "passive"))
      (node (ref "CN8") (pin "16") (pinfunction "16_16") (pintype "passive"))
    )
    (net (code "116") (name "/PG4") (class "Default")
      (node (ref "CN12") (pin "69") (pinfunction "69_69") (pintype "passive"))
      (node (ref "R69") (pin "1") (pinfunction "1_1") (pintype "passive"))
    )
    (net (code "117") (name "/PG5") (class "Default")
      (node (ref "CN12") (pin "68") (pinfunction "68_68") (pintype "passive"))
    )
    (net (code "118") (name "/PG6") (class "Default")
      (node (ref "CN10") (pin "13") (pinfunction "13_13") (pintype "passive"))
      (node (ref "CN12") (pin "70") (pinfunction "70_70") (pintype "passive"))
    )
    (net (code "119") (name "/PG7") (class "Default")
      (node (ref "CN12") (pin "67") (pinfunction "67_67") (pintype "passive"))
    )
    (net (code "120") (name "/PG8") (class "Default")
      (node (ref "CN12") (pin "66") (pinfunction "66_66") (pintype "passive"))
    )
    (net (code "121") (name "/PG9") (class "Default")
      (node (ref "CN11") (pin "63") (pinfunction "63_63") (pintype "passive"))
      (node (ref "CN7") (pin "12") (pinfunction "12_12") (pintype "passive"))
    )
    (net (code "122") (name "/PG10") (class "Default")
      (node (ref "CN11") (pin "66") (pinfunction "66_66") (pintype "passive"))
      (node (ref "CN7") (pin "17") (pinfunction "17_17") (pintype "passive"))
    )
    (net (code "123") (name "/PG11") (class "Default")
      (node (ref "CN11") (pin "70") (pinfunction "70_70") (pintype "passive"))
    )
    (net (code "124") (name "/PG12") (class "Default")
      (node (ref "CN10") (pin "2") (pinfunction "2_2") (pintype "passive"))
      (node (ref "CN11") (pin "65") (pinfunction "65_65") (pintype "passive"))
    )
    (net (code "125") (name "/PG13") (class "Default")
      (node (ref "CN11") (pin "68") (pinfunction "68_68") (pintype "passive"))
    )
    (net (code "126") (name "/PG14") (class "Default")
      (node (ref "CN10") (pin "12") (pinfunction "12_12") (pintype "passive"))
      (node (ref "CN12") (pin "61") (pinfunction "61_61") (pintype "passive"))
    )
    (net (code "127") (name "/PG15") (class "Default")
      (node (ref "CN11") (pin "64") (pinfunction "64_64") (pintype "passive"))
    )
    (net (code "129") (name "/PH0") (class "Default")
      (node (ref "CN11") (pin "29") (pinfunction "29_29") (pintype "passive"))
    )
    (net (code "130") (name "/PH1") (class "Default")
      (node (ref "CN11") (pin "31") (pinfunction "31_31") (pintype "passive"))
    )
    (net (code "132") (name "3V3") (class "Default")
      (node (ref "CN11") (pin "16") (pinfunction "16_16") (pintype "passive"))
      (node (ref "CN8") (pin "7") (pinfunction "7_7") (pintype "passive"))
      (node (ref "R24") (pin "2") (pinfunction "2_2") (pintype "passive"))
      (node (ref "R25") (pin "2") (pinfunction "2_2") (pintype "passive"))
      (node (ref "R26") (pin "2") (pinfunction "2_2") (pintype "passive"))
      (node (ref "SB25") (pin "1") (pinfunction "1_1") (pintype "passive"))
    )
    (net (code "133") (name "5V") (class "Default")
      (node (ref "CN11") (pin "18") (pinfunction "18_18") (pintype "passive"))
      (node (ref "CN8") (pin "9") (pinfunction "9_9") (pintype "passive"))
    )
    (net (code "134") (name "5V_EXT") (class "Default")
      (node (ref "CN11") (pin "6") (pinfunction "6_6") (pintype "passive"))
    )
    (net (code "135") (name "5V_STLK") (class "Default")
      (node (ref "CN12") (pin "8") (pinfunction "8_8") (pintype "passive"))
    )
    (net (code "136") (name "5V_VIN") (class "Default")
      (node (ref "R96") (pin "2") (pinfunction "2_2") (pintype "passive"))
    )
    (net (code "137") (name "AGND") (class "Default")
      (node (ref "C66") (pin "1") (pinfunction "1_1") (pintype "passive"))
      (node (ref "CN10") (pin "3") (pinfunction "3_3") (pintype "passive"))
      (node (ref "CN12") (pin "32") (pinfunction "32_32") (pintype "passive"))
    )
    (net (code "138") (name "GND") (class "Default")
      (node (ref "CN10") (pin "17") (pinfunction "17_17") (pintype "passive"))
      (node (ref "CN10") (pin "22") (pinfunction "22_22") (pintype "passive"))
      (node (ref "CN10") (pin "27") (pinfunction "27_27") (pintype "passive"))
      (node (ref "CN10") (pin "5") (pinfunction "5_5") (pintype "passive"))
      (node (ref "CN11") (pin "19") (pinfunction "19_19") (pintype "passive"))
      (node (ref "CN11") (pin "20") (pinfunction "20_20") (pintype "passive"))
      (node (ref "CN11") (pin "22") (pinfunction "22_22") (pintype "passive"))
      (node (ref "CN11") (pin "49") (pinfunction "49_49") (pintype "passive"))
      (node (ref "CN11") (pin "60") (pinfunction "60_60") (pintype "passive"))
      (node (ref "CN11") (pin "8") (pinfunction "8_8") (pintype "passive"))
      (node (ref "CN12") (pin "20") (pinfunction "20_20") (pintype "passive"))
      (node (ref "CN12") (pin "39") (pinfunction "39_39") (pintype "passive"))
      (node (ref "CN12") (pin "54") (pinfunction "54_54") (pintype "passive"))
      (node (ref "CN12") (pin "63") (pinfunction "63_63") (pintype "passive"))
      (node (ref "CN12") (pin "9") (pinfunction "9_9") (pintype "passive"))
      (node (ref "CN15") (pin "1") (pinfunction "COMMON_1") (pintype "passive"))
      (node (ref "CN15") (pin "2") (pinfunction "NO_2") (pintype "passive"))
      (node (ref "CN16") (pin "1") (pinfunction "COMMON_1") (pintype "passive"))
      (node (ref "CN16") (pin "2") (pinfunction "NO_2") (pintype "passive"))
      (node (ref "CN7") (pin "8") (pinfunction "8_8") (pintype "passive"))
      (node (ref "CN8") (pin "11") (pinfunction "11_11") (pintype "passive"))
      (node (ref "CN8") (pin "13") (pinfunction "13_13") (pintype "passive"))
      (node (ref "CN9") (pin "12") (pinfunction "12_12") (pintype "passive"))
      (node (ref "CN9") (pin "23") (pinfunction "23_23") (pintype "passive"))
      (node (ref "Q2") (pin "2") (pinfunction "E_2") (pintype "passive"))
      (node (ref "Q3") (pin "2") (pinfunction "E_2") (pintype "passive"))
      (node (ref "Q4") (pin "2") (pinfunction "E_2") (pintype "passive"))
      (node (ref "R65") (pin "1") (pinfunction "1_1") (pintype "passive"))
      (node (ref "R66") (pin "1") (pinfunction "1_1") (pintype "passive"))
      (node (ref "R67") (pin "1") (pinfunction "1_1") (pintype "passive"))
    )
    (net (code "139") (name "IOREF") (class "Default")
      (node (ref "CN11") (pin "12") (pinfunction "12_12") (pintype "passive"))
      (node (ref "CN8") (pin "3") (pinfunction "3_3") (pintype "passive"))
      (node (ref "SB16") (pin "2") (pinfunction "2_2") (pintype "passive"))
      (node (ref "SB25") (pin "2") (pinfunction "2_2") (pintype "passive"))
    )
    (net (code "140") (name "Net-(CN7-Pad3)") (class "Default")
      (node (ref "CN7") (pin "3") (pinfunction "3_3") (pintype "passive"))
      (node (ref "SB10") (pin "2") (pinfunction "2_2") (pintype "passive"))
    )
    (net (code "141") (name "Net-(CN7-Pad5)") (class "Default")
      (node (ref "CN7") (pin "5") (pinfunction "5_5") (pintype "passive"))
      (node (ref "SB12") (pin "2") (pinfunction "2_2") (pintype "passive"))
    )
    (net (code "142") (name "Net-(CN7-Pad13)") (class "Default")
      (node (ref "CN7") (pin "13") (pinfunction "13_13") (pintype "passive"))
      (node (ref "SB17") (pin "2") (pinfunction "2_2") (pintype "passive"))
    )
    (net (code "143") (name "Net-(CN7-Pad14)") (class "Default")
      (node (ref "CN7") (pin "14") (pinfunction "14_14") (pintype "passive"))
      (node (ref "SB41") (pin "1") (pinfunction "1_1") (pintype "passive"))
    )
    (net (code "144") (name "Net-(CN7-Pad15)") (class "Default")
      (node (ref "CN7") (pin "15") (pinfunction "15_15") (pintype "passive"))
      (node (ref "SB33") (pin "2") (pinfunction "2_2") (pintype "passive"))
    )
    (net (code "145") (name "Net-(CN8-Pad1)") (class "Default")
      (node (ref "CN8") (pin "1") (pinfunction "1_1") (pintype "passive"))
      (node (ref "R96") (pin "1") (pinfunction "1_1") (pintype "passive"))
    )
    (net (code "146") (name "Net-(CN9-Pad9)") (class "Default")
      (node (ref "CN9") (pin "9") (pinfunction "9_9") (pintype "passive"))
      (node (ref "SB52") (pin "2") (pinfunction "2_2") (pintype "passive"))
      (node (ref "SB53") (pin "2") (pinfunction "2_2") (pintype "passive"))
    )
    (net (code "147") (name "Net-(CN9-Pad11)") (class "Default")
      (node (ref "CN9") (pin "11") (pinfunction "11_11") (pintype "passive"))
      (node (ref "SB57") (pin "2") (pinfunction "2_2") (pintype "passive"))
      (node (ref "SB60") (pin "2") (pinfunction "2_2") (pintype "passive"))
    )
    (net (code "148") (name "Net-(CN9-Pad13)") (class "Default")
      (node (ref "CN9") (pin "13") (pinfunction "13_13") (pintype "passive"))
      (node (ref "SB66") (pin "2") (pinfunction "2_2") (pintype "passive"))
    )
    (net (code "149") (name "Net-(CN9-Pad15)") (class "Default")
      (node (ref "CN9") (pin "15") (pinfunction "15_15") (pintype "passive"))
      (node (ref "SB67") (pin "2") (pinfunction "2_2") (pintype "passive"))
    )
    (net (code "150") (name "Net-(CN10-Pad4)") (class "Default")
      (node (ref "CN10") (pin "4") (pinfunction "4_4") (pintype "passive"))
      (node (ref "SB35") (pin "1") (pinfunction "1_1") (pintype "passive"))
    )
    (net (code "151") (name "Net-(CN10-Pad15)") (class "Default")
      (node (ref "CN10") (pin "15") (pinfunction "15_15") (pintype "passive"))
      (node (ref "SB61") (pin "2") (pinfunction "2_2") (pintype "passive"))
    )
    (net (code "152") (name "Net-(CN10-Pad25)") (class "Default")
      (node (ref "CN10") (pin "25") (pinfunction "25_25") (pintype "passive"))
      (node (ref "SB70") (pin "2") (pinfunction "2_2") (pintype "passive"))
    )
    (net (code "153") (name "Net-(CN10-Pad28)") (class "Default")
      (node (ref "CN10") (pin "28") (pinfunction "28_28") (pintype "passive"))
      (node (ref "SB71") (pin "1") (pinfunction "1_1") (pintype "passive"))
    )
    (net (code "154") (name "Net-(CN10-Pad29)") (class "Default")
      (node (ref "CN10") (pin "29") (pinfunction "29_29") (pintype "passive"))
      (node (ref "SB73") (pin "2") (pinfunction "2_2") (pintype "passive"))
    )
    (net (code "155") (name "Net-(CN11-Pad69)") (class "Default")
      (node (ref "CN11") (pin "69") (pinfunction "69_69") (pintype "passive"))
      (node (ref "SB75") (pin "2") (pinfunction "2_2") (pintype "passive"))
    )
    (net (code "156") (name "Net-(CN12-Pad1)") (class "Default")
      (node (ref "CN12") (pin "1") (pinfunction "1_1") (pintype "passive"))
      (node (ref "SB20") (pin "2") (pinfunction "2_2") (pintype "passive"))
    )
    (net (code "157") (name "Net-(CN12-Pad2)") (class "Default")
      (node (ref "CN12") (pin "2") (pinfunction "2_2") (pintype "passive"))
      (node (ref "SB19") (pin "1") (pinfunction "1_1") (pintype "passive"))
    )
    (net (code "158") (name "Net-(CN12-Pad7)") (class "Default")
      (node (ref "CN12") (pin "7") (pinfunction "7_7") (pintype "passive"))
      (node (ref "CN7") (pin "6") (pinfunction "6_6") (pintype "passive"))
      (node (ref "SB46") (pin "1") (pinfunction "1_1") (pintype "passive"))
    )
    (net (code "159") (name "Net-(CN12-Pad10)") (class "Default")
      (node (ref "CN12") (pin "10") (pinfunction "10_10") (pintype "passive"))
      (node (ref "SB13") (pin "1") (pinfunction "1_1") (pintype "passive"))
    )
    (net (code "160") (name "Net-(CN12-Pad12)") (class "Default")
      (node (ref "CN12") (pin "12") (pinfunction "12_12") (pintype "passive"))
      (node (ref "SB22") (pin "1") (pinfunction "1_1") (pintype "passive"))
    )
    (net (code "161") (name "Net-(CN12-Pad14)") (class "Default")
      (node (ref "CN12") (pin "14") (pinfunction "14_14") (pintype "passive"))
      (node (ref "SB21") (pin "1") (pinfunction "1_1") (pintype "passive"))
    )
    (net (code "162") (name "Net-(LD1-Pad1)") (class "Default")
      (node (ref "LD1") (pin "1") (pintype "passive"))
      (node (ref "R24") (pin "1") (pinfunction "1_1") (pintype "passive"))
    )
    (net (code "163") (name "Net-(LD2-Pad1)") (class "Default")
      (node (ref "LD2") (pin "1") (pintype "passive"))
      (node (ref "R26") (pin "1") (pinfunction "1_1") (pintype "passive"))
    )
    (net (code "164") (name "Net-(LD3-Pad1)") (class "Default")
      (node (ref "LD3") (pin "1") (pintype "passive"))
      (node (ref "R25") (pin "1") (pinfunction "1_1") (pintype "passive"))
    )
    (net (code "165") (name "Net-(Q2-B)") (class "Default")
      (node (ref "Q2") (pin "1") (pinfunction "B_1") (pintype "passive"))
      (node (ref "R65") (pin "2") (pinfunction "2_2") (pintype "passive"))
      (node (ref "R70") (pin "2") (pinfunction "2_2") (pintype "passive"))
    )
    (net (code "166") (name "Net-(Q2-C)") (class "Default")
      (node (ref "LD1") (pin "2") (pintype "passive"))
      (node (ref "Q2") (pin "3") (pinfunction "C_3") (pintype "passive"))
    )
    (net (code "167") (name "Net-(Q3-B)") (class "Default")
      (node (ref "Q3") (pin "1") (pinfunction "B_1") (pintype "passive"))
      (node (ref "R66") (pin "2") (pinfunction "2_2") (pintype "passive"))
      (node (ref "R68") (pin "2") (pinfunction "2_2") (pintype "passive"))
    )
    (net (code "168") (name "Net-(Q3-C)") (class "Default")
      (node (ref "LD2") (pin "2") (pintype "passive"))
      (node (ref "Q3") (pin "3") (pinfunction "C_3") (pintype "passive"))
    )
    (net (code "169") (name "Net-(Q4-B)") (class "Default")
      (node (ref "Q4") (pin "1") (pinfunction "B_1") (pintype "passive"))
      (node (ref "R67") (pin "2") (pinfunction "2_2") (pintype "passive"))
      (node (ref "R69") (pin "2") (pinfunction "2_2") (pintype "passive"))
    )
    (net (code "170") (name "Net-(Q4-C)") (class "Default")
      (node (ref "LD3") (pin "2") (pintype "passive"))
      (node (ref "Q4") (pin "3") (pinfunction "C_3") (pintype "passive"))
    )
    (net (code "171") (name "Net-(R70-Pad1)") (class "Default")
      (node (ref "R70") (pin "1") (pinfunction "1_1") (pintype "passive"))
      (node (ref "SB43") (pin "2") (pinfunction "2_2") (pintype "passive"))
      (node (ref "SB51") (pin "2") (pinfunction "2_2") (pintype "passive"))
    )
    (net (code "172") (name "VBAT") (class "Default")
      (node (ref "CN11") (pin "33") (pinfunction "33_33") (pintype "passive"))
    )
    (net (code "173") (name "VDD") (class "Default")
      (node (ref "CN11") (pin "5") (pinfunction "5_5") (pintype "passive"))
      (node (ref "SB16") (pin "1") (pinfunction "1_1") (pintype "passive"))
    )
    (net (code "174") (name "VDDA") (class "Default")
      (node (ref "CN10") (pin "1") (pinfunction "1_1") (pintype "passive"))
    )
    (net (code "175") (name "VIN") (class "Default")
      (node (ref "CN11") (pin "24") (pinfunction "24_24") (pintype "passive"))
      (node (ref "CN8") (pin "15") (pinfunction "15_15") (pintype "passive"))
    )
    (net (code "176") (name "VREFP") (class "Default")
      (node (ref "C66") (pin "2") (pinfunction "2_2") (pintype "passive"))
      (node (ref "SB46") (pin "2") (pinfunction "2_2") (pintype "passive"))
    )
    (net (code "177") (name "unconnected-(CN11-Pad10)") (class "Default")
      (node (ref "CN11") (pin "10") (pinfunction "10_10") (pintype "passive+no_connect"))
    )
    (net (code "178") (name "unconnected-(CN11-Pad26)") (class "Default")
      (node (ref "CN11") (pin "26") (pinfunction "26_26") (pintype "passive+no_connect"))
    )
    (net (code "179") (name "unconnected-(CN11-Pad61)") (class "Default")
      (node (ref "CN11") (pin "61") (pinfunction "61_61") (pintype "passive+no_connect"))
    )
    (net (code "180") (name "unconnected-(CN11-Pad67)") (class "Default")
      (node (ref "CN11") (pin "67") (pinfunction "67_67") (pintype "passive+no_connect"))
    )
    (net (code "181") (name "unconnected-(CN12-Pad18)") (class "Default")
      (node (ref "CN12") (pin "18") (pinfunction "18_18") (pintype "passive+no_connect"))
    )
  )
)
